# MPU6050.net
KiCad netlist of a schematic drawn in Altium Designer
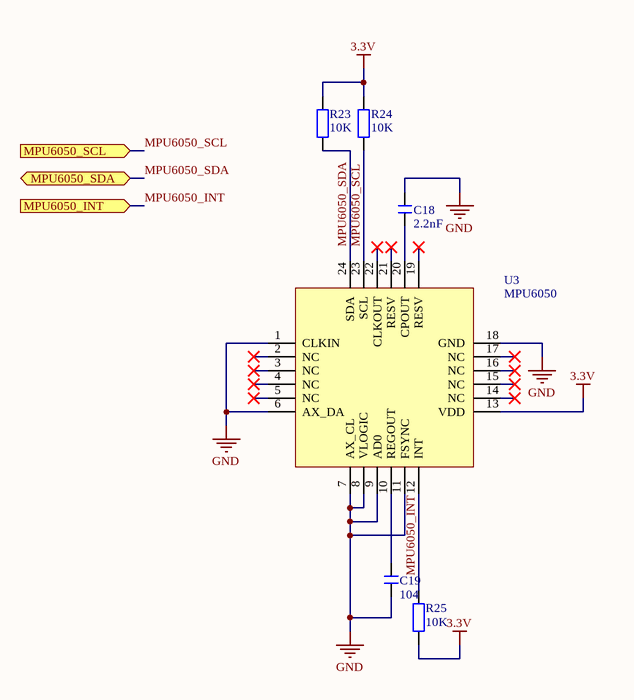
[diagram p0: MPU6050六轴模块.SchDoc]

(export (version "E")
  (design (tool "Eeschema 10.0.6"))
  (components
    (comp (ref "C18")
      (value "2.2nF")
      (footprint "C 0603_L")
      (description "无极性贴片电容")
      (fields (field (name "版权归属") "黎明电子style"))
      (libsource (lib "3.3   - 电容capacitor") (part "C"))
    )
    (comp (ref "C19")
      (value "104")
      (footprint "C 0603_L")
      (description "无极性贴片电容")
      (fields (field (name "版权归属") "黎明电子style"))
      (libsource (lib "3.3   - 电容capacitor") (part "C"))
    )
    (comp (ref "R23")
      (value "10K")
      (footprint "R 0603_L")
      (description "贴片电阻")
      (fields (field (name "版权归属") "黎明电子style"))
      (libsource (lib "3.4   - 电阻Resistor") (part "R"))
    )
    (comp (ref "R24")
      (value "10K")
      (footprint "R 0603_L")
      (description "贴片电阻")
      (fields (field (name "版权归属") "黎明电子style"))
      (libsource (lib "3.4   - 电阻Resistor") (part "R"))
    )
    (comp (ref "R25")
      (value "10K")
      (footprint "R 0603_L")
      (description "贴片电阻")
      (fields (field (name "版权归属") "黎明电子style"))
      (libsource (lib "3.4   - 电阻Resistor") (part "R"))
    )
    (comp (ref "U3")
      (value "MPU6050")
      (footprint "QFN24 4x4_L")
      (description "数字运动传感器")
      (fields (field (name "版权归属") "源创客"))
      (libsource (lib "11.1 - 传感元件") (part "MPU6050"))
    )
  )
  (nets
    (net (code "1") (name "/MPU6050_INT") (class "Default")
      (node (ref "R25") (pin "2") (pinfunction "2_2") (pintype "passive"))
      (node (ref "U3") (pin "12") (pinfunction "INT_12") (pintype "passive"))
    )
    (net (code "2") (name "/MPU6050_SCL") (class "Default")
      (node (ref "R24") (pin "1") (pinfunction "1_1") (pintype "passive"))
      (node (ref "U3") (pin "23") (pinfunction "SCL_23") (pintype "passive"))
    )
    (net (code "3") (name "/MPU6050_SDA") (class "Default")
      (node (ref "R23") (pin "1") (pinfunction "1_1") (pintype "passive"))
      (node (ref "U3") (pin "24") (pinfunction "SDA_24") (pintype "passive"))
    )
    (net (code "4") (name "3.3V") (class "Default")
      (node (ref "R23") (pin "2") (pinfunction "2_2") (pintype "passive"))
      (node (ref "R24") (pin "2") (pinfunction "2_2") (pintype "passive"))
      (node (ref "R25") (pin "1") (pinfunction "1_1") (pintype "passive"))
      (node (ref "U3") (pin "13") (pinfunction "VDD_13") (pintype "passive"))
    )
    (net (code "5") (name "GND") (class "Default")
      (node (ref "C18") (pin "2") (pinfunction "2_2") (pintype "passive"))
      (node (ref "C19") (pin "1") (pinfunction "1_1") (pintype "passive"))
      (node (ref "U3") (pin "1") (pinfunction "CLKIN_1") (pintype "passive"))
      (node (ref "U3") (pin "11") (pinfunction "FSYNC_11") (pintype "passive"))
      (node (ref "U3") (pin "18") (pinfunction "GND_18") (pintype "passive"))
      (node (ref "U3") (pin "6") (pinfunction "AX_DA_6") (pintype "passive"))
      (node (ref "U3") (pin "7") (pinfunction "AX_CL_7") (pintype "passive"))
      (node (ref "U3") (pin "8") (pinfunction "VLOGIC_8") (pintype "passive"))
      (node (ref "U3") (pin "9") (pinfunction "AD0_9") (pintype "passive"))
    )
    (net (code "6") (name "Net-(U3-CPOUT)") (class "Default")
      (node (ref "C18") (pin "1") (pinfunction "1_1") (pintype "passive"))
      (node (ref "U3") (pin "20") (pinfunction "CPOUT_20") (pintype "passive"))
    )
    (net (code "7") (name "Net-(U3-REGOUT)") (class "Default")
      (node (ref "C19") (pin "2") (pinfunction "2_2") (pintype "passive"))
      (node (ref "U3") (pin "10") (pinfunction "REGOUT_10") (pintype "passive"))
    )
    (net (code "8") (name "unconnected-(U3-CLKOUT-Pad22)") (class "Default")
      (node (ref "U3") (pin "22") (pinfunction "CLKOUT_22") (pintype "passive+no_connect"))
    )
    (net (code "9") (name "unconnected-(U3-NC-Pad2)") (class "Default")
      (node (ref "U3") (pin "2") (pinfunction "NC_2") (pintype "passive+no_connect"))
    )
    (net (code "10") (name "unconnected-(U3-NC-Pad3)") (class "Default")
      (node (ref "U3") (pin "3") (pinfunction "NC_3") (pintype "passive+no_connect"))
    )
    (net (code "11") (name "unconnected-(U3-NC-Pad4)") (class "Default")
      (node (ref "U3") (pin "4") (pinfunction "NC_4") (pintype "passive+no_connect"))
    )
    (net (code "12") (name "unconnected-(U3-NC-Pad5)") (class "Default")
      (node (ref "U3") (pin "5") (pinfunction "NC_5") (pintype "passive+no_connect"))
    )
    (net (code "13") (name "unconnected-(U3-NC-Pad14)") (class "Default")
      (node (ref "U3") (pin "14") (pinfunction "NC_14") (pintype "passive+no_connect"))
    )
    (net (code "14") (name "unconnected-(U3-NC-Pad15)") (class "Default")
      (node (ref "U3") (pin "15") (pinfunction "NC_15") (pintype "passive+no_connect"))
    )
    (net (code "15") (name "unconnected-(U3-NC-Pad16)") (class "Default")
      (node (ref "U3") (pin "16") (pinfunction "NC_16") (pintype "passive+no_connect"))
    )
    (net (code "16") (name "unconnected-(U3-NC-Pad17)") (class "Default")
      (node (ref "U3") (pin "17") (pinfunction "NC_17") (pintype "passive+no_connect"))
    )
    (net (code "17") (name "unconnected-(U3-RESV-Pad19)") (class "Default")
      (node (ref "U3") (pin "19") (pinfunction "RESV_19") (pintype "passive+no_connect"))
    )
    (net (code "18") (name "unconnected-(U3-RESV-Pad21)") (class "Default")
      (node (ref "U3") (pin "21") (pinfunction "RESV_21") (pintype "passive+no_connect"))
    )
  )
)
